# NovaHammyRevXD.net
KiCad netlist of a schematic drawn in EAGLE
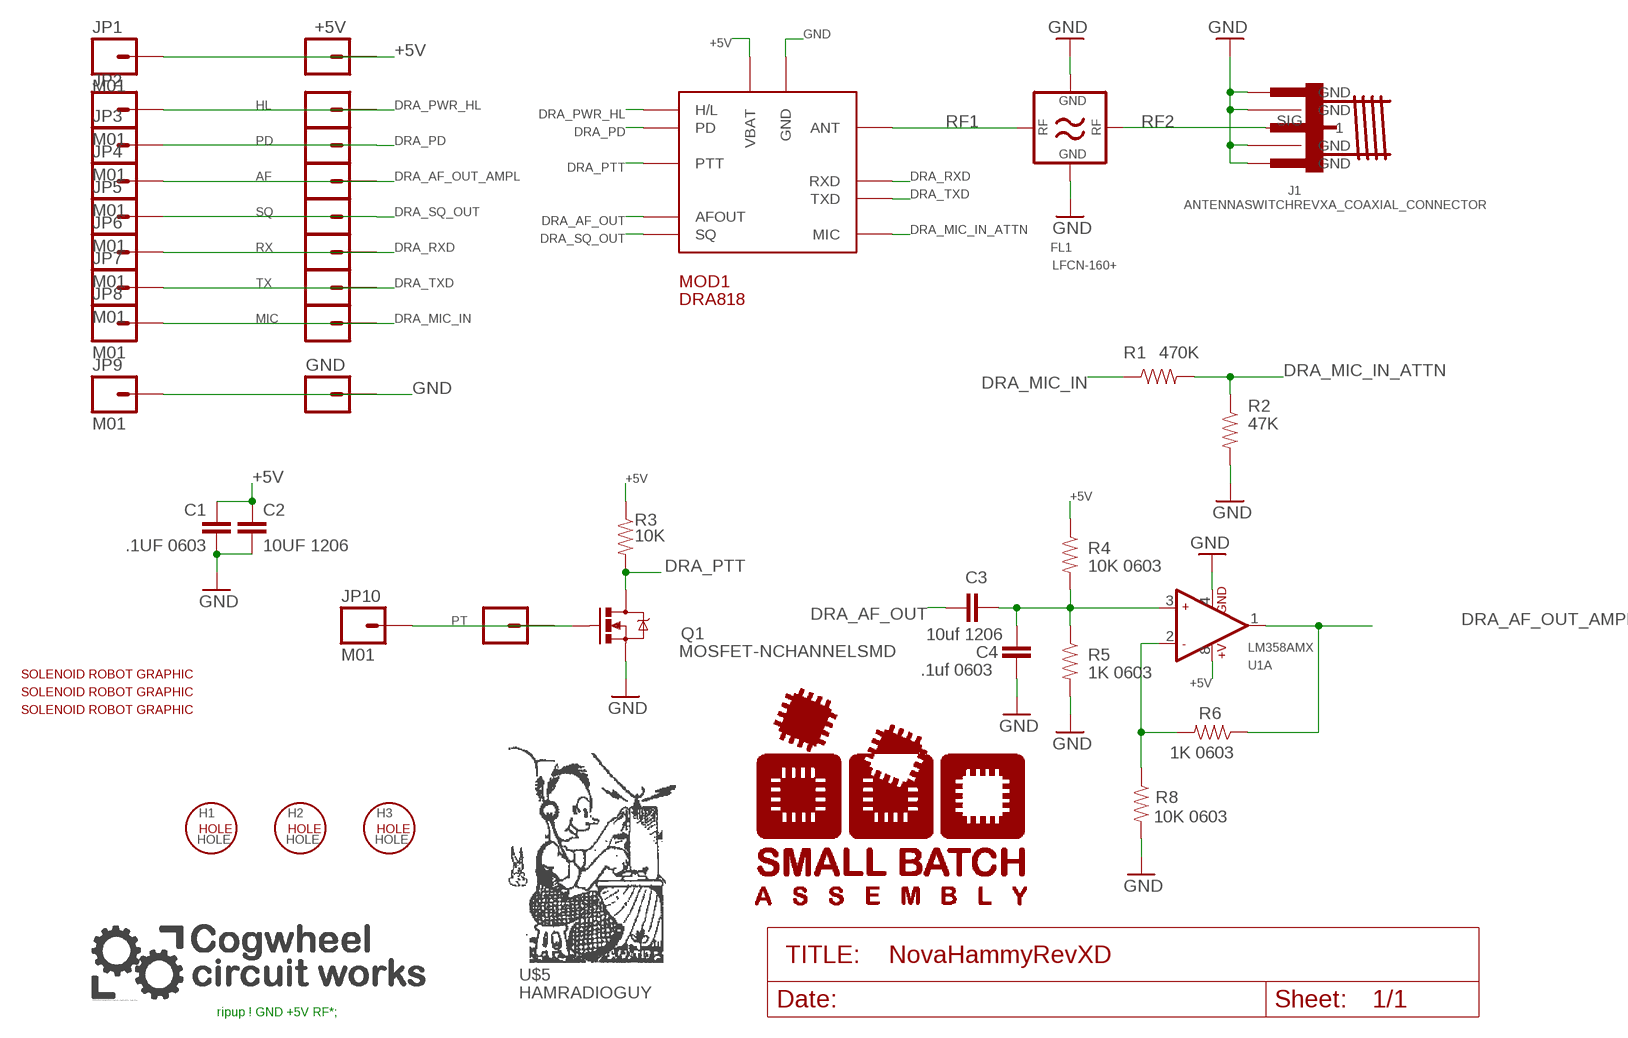
[diagram p0: schematic, sheet 1]

(export (version "E")
  (design (tool "Eeschema 10.0.6"))
  (components
    (comp (ref "5V")
      (value "+5V")
      (footprint "eagle-import:1X01_NO_SILK")
      (libsource (lib "eagle-import") (part "M01PTH_NO_SILK_YES_STOP"))
    )
    (comp (ref "AF")
      (value "M01PTH_NO_SILK_YES_STOP")
      (footprint "eagle-import:1X01_NO_SILK")
      (libsource (lib "eagle-import") (part "M01PTH_NO_SILK_YES_STOP"))
    )
    (comp (ref "C1")
      (value ".1UF 0603")
      (footprint "eagle-import:0603")
      (libsource (lib "eagle-import") (part "CAP0603"))
    )
    (comp (ref "C2")
      (value "10UF 1206")
      (footprint "eagle-import:1206")
      (libsource (lib "eagle-import") (part "CAP1206"))
    )
    (comp (ref "C3")
      (value "10uf 1206")
      (footprint "eagle-import:1206")
      (libsource (lib "eagle-import") (part "CAP1206"))
    )
    (comp (ref "C4")
      (value ".1uf 0603")
      (footprint "eagle-import:0603")
      (libsource (lib "eagle-import") (part "CAP0603"))
    )
    (comp (ref "FL1")
      (value "LFCN-160+")
      (footprint "eagle-import:FV1206")
      (libsource (lib "eagle-import") (part "LFCN-XXX"))
    )
    (comp (ref "GND")
      (value "M01PTH_NO_SILK_YES_STOP")
      (footprint "eagle-import:1X01_NO_SILK")
      (libsource (lib "eagle-import") (part "M01PTH_NO_SILK_YES_STOP"))
    )
    (comp (ref "H1")
      (value "HOLE")
      (footprint "eagle-import:HOLE_3.3MM_M3_HEX_BOLT")
      (libsource (lib "eagle-import") (part "HOLE"))
    )
    (comp (ref "H2")
      (value "HOLE")
      (footprint "eagle-import:HOLE_3.3MM_M3_HEX_BOLT")
      (libsource (lib "eagle-import") (part "HOLE"))
    )
    (comp (ref "H3")
      (value "HOLE")
      (footprint "eagle-import:HOLE_3.3MM_M3_HEX_BOLT")
      (libsource (lib "eagle-import") (part "HOLE"))
    )
    (comp (ref "HL")
      (value "M01PTH_NO_SILK_YES_STOP")
      (footprint "eagle-import:1X01_NO_SILK")
      (libsource (lib "eagle-import") (part "M01PTH_NO_SILK_YES_STOP"))
    )
    (comp (ref "J1")
      (value "ANTENNASWITCHREVXA_COAXIAL_CONNECTOR")
      (footprint "eagle-import:ANTENNASWITCHREVXA_SMA_JACK_EDGE_MOUNT")
      (libsource (lib "eagle-import") (part "ANTENNASWITCHREVXA_COAXIAL_CONNECTOR"))
    )
    (comp (ref "JP1")
      (value "M01")
      (footprint "eagle-import:1X01_SMT_2MM")
      (libsource (lib "eagle-import") (part "M01"))
    )
    (comp (ref "JP2")
      (value "M01")
      (footprint "eagle-import:1X01_SMT_2MM")
      (libsource (lib "eagle-import") (part "M01"))
    )
    (comp (ref "JP3")
      (value "M01")
      (footprint "eagle-import:1X01_SMT_2MM")
      (libsource (lib "eagle-import") (part "M01"))
    )
    (comp (ref "JP4")
      (value "M01")
      (footprint "eagle-import:1X01_SMT_2MM")
      (libsource (lib "eagle-import") (part "M01"))
    )
    (comp (ref "JP5")
      (value "M01")
      (footprint "eagle-import:1X01_SMT_2MM")
      (libsource (lib "eagle-import") (part "M01"))
    )
    (comp (ref "JP6")
      (value "M01")
      (footprint "eagle-import:1X01_SMT_2MM")
      (libsource (lib "eagle-import") (part "M01"))
    )
    (comp (ref "JP7")
      (value "M01")
      (footprint "eagle-import:1X01_SMT_2MM")
      (libsource (lib "eagle-import") (part "M01"))
    )
    (comp (ref "JP8")
      (value "M01")
      (footprint "eagle-import:1X01_SMT_2MM")
      (libsource (lib "eagle-import") (part "M01"))
    )
    (comp (ref "JP9")
      (value "M01")
      (footprint "eagle-import:1X01_SMT_2MM")
      (libsource (lib "eagle-import") (part "M01"))
    )
    (comp (ref "JP10")
      (value "M01")
      (footprint "eagle-import:1X01_SMT_2MM")
      (libsource (lib "eagle-import") (part "M01"))
    )
    (comp (ref "MIC")
      (value "M01PTH_NO_SILK_YES_STOP")
      (footprint "eagle-import:1X01_NO_SILK")
      (libsource (lib "eagle-import") (part "M01PTH_NO_SILK_YES_STOP"))
    )
    (comp (ref "MOD1")
      (value "DRA818")
      (footprint "eagle-import:DRA818")
      (libsource (lib "eagle-import") (part "DRA818"))
    )
    (comp (ref "PD")
      (value "M01PTH_NO_SILK_YES_STOP")
      (footprint "eagle-import:1X01_NO_SILK")
      (libsource (lib "eagle-import") (part "M01PTH_NO_SILK_YES_STOP"))
    )
    (comp (ref "PT")
      (value "M01PTH_NO_SILK_YES_STOP")
      (footprint "eagle-import:1X01_NO_SILK")
      (libsource (lib "eagle-import") (part "M01PTH_NO_SILK_YES_STOP"))
    )
    (comp (ref "Q1")
      (value "MOSFET-NCHANNELSMD")
      (footprint "eagle-import:SOT23-3")
      (libsource (lib "eagle-import") (part "MOSFET-NCHANNELSMD"))
    )
    (comp (ref "R1")
      (value "470K")
      (footprint "eagle-import:0603")
      (libsource (lib "eagle-import") (part "RES0603"))
    )
    (comp (ref "R2")
      (value "47K")
      (footprint "eagle-import:0603")
      (libsource (lib "eagle-import") (part "RES0603"))
    )
    (comp (ref "R3")
      (value "10K")
      (footprint "eagle-import:0603")
      (libsource (lib "eagle-import") (part "RES0603"))
    )
    (comp (ref "R4")
      (value "10K 0603")
      (footprint "eagle-import:0603")
      (libsource (lib "eagle-import") (part "RES0603"))
    )
    (comp (ref "R5")
      (value "1K 0603")
      (footprint "eagle-import:0603")
      (libsource (lib "eagle-import") (part "RES0603"))
    )
    (comp (ref "R6")
      (value "1K 0603")
      (footprint "eagle-import:0603")
      (libsource (lib "eagle-import") (part "RES0603"))
    )
    (comp (ref "R8")
      (value "10K 0603")
      (footprint "eagle-import:0603")
      (libsource (lib "eagle-import") (part "RES0603"))
    )
    (comp (ref "RX")
      (value "M01PTH_NO_SILK_YES_STOP")
      (footprint "eagle-import:1X01_NO_SILK")
      (libsource (lib "eagle-import") (part "M01PTH_NO_SILK_YES_STOP"))
    )
    (comp (ref "SQ")
      (value "M01PTH_NO_SILK_YES_STOP")
      (footprint "eagle-import:1X01_NO_SILK")
      (libsource (lib "eagle-import") (part "M01PTH_NO_SILK_YES_STOP"))
    )
    (comp (ref "TX")
      (value "M01PTH_NO_SILK_YES_STOP")
      (footprint "eagle-import:1X01_NO_SILK")
      (libsource (lib "eagle-import") (part "M01PTH_NO_SILK_YES_STOP"))
    )
    (comp (ref "U$1")
      (value "SOLENOID_ROBOTSML")
      (footprint "eagle-import:SOLENOID_ROBOT")
      (libsource (lib "eagle-import") (part "SOLENOID_ROBOTSML"))
    )
    (comp (ref "U$2")
      (value "SOLENOID_ROBOTSML")
      (footprint "eagle-import:SOLENOID_ROBOT")
      (libsource (lib "eagle-import") (part "SOLENOID_ROBOTSML"))
    )
    (comp (ref "U$3")
      (value "SOLENOID_ROBOTSML")
      (footprint "eagle-import:SOLENOID_ROBOT")
      (libsource (lib "eagle-import") (part "SOLENOID_ROBOTSML"))
    )
    (comp (ref "U$4")
      (value "SMALLBATCH_LOGOA")
      (footprint "eagle-import:SMALLBATCH_750W_V2")
      (libsource (lib "eagle-import") (part "SMALLBATCH_LOGOA"))
    )
    (comp (ref "U$5")
      (value "HAMRADIOGUY")
      (footprint "eagle-import:HAMRADIO_3Q_INCH")
      (libsource (lib "eagle-import") (part "HAMRADIOGUY"))
    )
    (comp (ref "U$6")
      (value "CWILOGO")
      (footprint "eagle-import:CWORKSLOGO_750MIL_WIDE_400DPI")
      (libsource (lib "eagle-import") (part "CWILOGO"))
    )
    (comp (ref "U1")
      (value "LM358AMX")
      (footprint "eagle-import:SOIC8")
      (libsource (lib "eagle-import") (part "LM358DR-1110010P1"))
    )
  )
  (nets
    (net (code "1") (name "/+5V") (class "Default")
      (node (ref "5V") (pin "1") (pinfunction "1_1") (pintype "passive"))
      (node (ref "C1") (pin "2") (pinfunction "2_2") (pintype "passive"))
      (node (ref "C2") (pin "1") (pinfunction "1_1") (pintype "passive"))
      (node (ref "JP1") (pin "P$1") (pinfunction "1_P$1") (pintype "passive"))
      (node (ref "MOD1") (pin "P$8") (pinfunction "VBAT_P$8") (pintype "bidirectional"))
      (node (ref "R3") (pin "1") (pinfunction "1_1") (pintype "passive"))
      (node (ref "R4") (pin "1") (pinfunction "1_1") (pintype "passive"))
      (node (ref "U1") (pin "8") (pinfunction "+V_8") (pintype "power_in"))
    )
    (net (code "2") (name "/DRA_AF_OUT") (class "Default")
      (node (ref "C3") (pin "1") (pinfunction "1_1") (pintype "passive"))
      (node (ref "MOD1") (pin "P$3") (pinfunction "AFOUT_P$3") (pintype "bidirectional"))
    )
    (net (code "3") (name "/DRA_AF_OUT_AMPL") (class "Default")
      (node (ref "AF") (pin "1") (pinfunction "1_1") (pintype "passive"))
      (node (ref "JP4") (pin "P$1") (pinfunction "1_P$1") (pintype "passive"))
      (node (ref "R6") (pin "1") (pinfunction "1_1") (pintype "passive"))
      (node (ref "U1") (pin "1") (pinfunction "OUT1_1") (pintype "output"))
    )
    (net (code "4") (name "/DRA_MIC_IN") (class "Default")
      (node (ref "JP8") (pin "P$1") (pinfunction "1_P$1") (pintype "passive"))
      (node (ref "MIC") (pin "1") (pinfunction "1_1") (pintype "passive"))
      (node (ref "R1") (pin "1") (pinfunction "1_1") (pintype "passive"))
    )
    (net (code "5") (name "/DRA_MIC_IN_ATTN") (class "Default")
      (node (ref "MOD1") (pin "P$18") (pinfunction "MIC_P$18") (pintype "bidirectional"))
      (node (ref "R1") (pin "2") (pinfunction "2_2") (pintype "passive"))
      (node (ref "R2") (pin "1") (pinfunction "1_1") (pintype "passive"))
    )
    (net (code "6") (name "/DRA_PD") (class "Default")
      (node (ref "JP3") (pin "P$1") (pinfunction "1_P$1") (pintype "passive"))
      (node (ref "MOD1") (pin "P$6") (pinfunction "PD_P$6") (pintype "bidirectional"))
      (node (ref "PD") (pin "1") (pinfunction "1_1") (pintype "passive"))
    )
    (net (code "7") (name "/DRA_PTT") (class "Default")
      (node (ref "MOD1") (pin "P$5") (pinfunction "PTT_P$5") (pintype "bidirectional"))
      (node (ref "Q1") (pin "3") (pinfunction "D_3") (pintype "passive"))
      (node (ref "R3") (pin "2") (pinfunction "2_2") (pintype "passive"))
    )
    (net (code "8") (name "/DRA_PWR_HL") (class "Default")
      (node (ref "HL") (pin "1") (pinfunction "1_1") (pintype "passive"))
      (node (ref "JP2") (pin "P$1") (pinfunction "1_P$1") (pintype "passive"))
      (node (ref "MOD1") (pin "P$7") (pinfunction "H/L_P$7") (pintype "bidirectional"))
    )
    (net (code "9") (name "/DRA_RXD") (class "Default")
      (node (ref "JP6") (pin "P$1") (pinfunction "1_P$1") (pintype "passive"))
      (node (ref "MOD1") (pin "P$16") (pinfunction "RXD_P$16") (pintype "bidirectional"))
      (node (ref "RX") (pin "1") (pinfunction "1_1") (pintype "passive"))
    )
    (net (code "10") (name "/DRA_SQ_OUT") (class "Default")
      (node (ref "JP5") (pin "P$1") (pinfunction "1_P$1") (pintype "passive"))
      (node (ref "MOD1") (pin "P$1") (pinfunction "SQ_P$1") (pintype "bidirectional"))
      (node (ref "SQ") (pin "1") (pinfunction "1_1") (pintype "passive"))
    )
    (net (code "11") (name "/DRA_TXD") (class "Default")
      (node (ref "JP7") (pin "P$1") (pinfunction "1_P$1") (pintype "passive"))
      (node (ref "MOD1") (pin "P$17") (pinfunction "TXD_P$17") (pintype "bidirectional"))
      (node (ref "TX") (pin "1") (pinfunction "1_1") (pintype "passive"))
    )
    (net (code "12") (name "/RF1") (class "Default")
      (node (ref "FL1") (pin "1") (pinfunction "IO1_1") (pintype "passive"))
      (node (ref "MOD1") (pin "P$12") (pinfunction "ANT_P$12") (pintype "bidirectional"))
    )
    (net (code "13") (name "/RF2") (class "Default")
      (node (ref "FL1") (pin "3") (pinfunction "IO2_3") (pintype "passive"))
      (node (ref "J1") (pin "SIG") (pinfunction "1_SIG") (pintype "passive"))
    )
    (net (code "14") (name "GND") (class "Default")
      (node (ref "C1") (pin "1") (pinfunction "1_1") (pintype "passive"))
      (node (ref "C2") (pin "2") (pinfunction "2_2") (pintype "passive"))
      (node (ref "C4") (pin "2") (pinfunction "2_2") (pintype "passive"))
      (node (ref "FL1") (pin "11") (pinfunction "GND2_11") (pintype "passive"))
      (node (ref "FL1") (pin "12") (pinfunction "GND2_12") (pintype "passive"))
      (node (ref "FL1") (pin "13") (pinfunction "GND2_13") (pintype "passive"))
      (node (ref "FL1") (pin "14") (pinfunction "GND2_14") (pintype "passive"))
      (node (ref "FL1") (pin "2") (pinfunction "GND2_2") (pintype "passive"))
      (node (ref "FL1") (pin "4") (pinfunction "GND1_4") (pintype "passive"))
      (node (ref "FL1") (pin "6") (pinfunction "GND1_6") (pintype "passive"))
      (node (ref "FL1") (pin "7") (pinfunction "GND1_7") (pintype "passive"))
      (node (ref "FL1") (pin "8") (pinfunction "GND1_8") (pintype "passive"))
      (node (ref "FL1") (pin "9") (pinfunction "GND1_9") (pintype "passive"))
      (node (ref "GND") (pin "1") (pinfunction "1_1") (pintype "passive"))
      (node (ref "J1") (pin "G") (pinfunction "GND_G") (pintype "passive"))
      (node (ref "J1") (pin "G2") (pinfunction "GND_G2") (pintype "passive"))
      (node (ref "J1") (pin "G3") (pinfunction "GND_G3") (pintype "passive"))
      (node (ref "J1") (pin "G4") (pinfunction "GND_G4") (pintype "passive"))
      (node (ref "JP9") (pin "P$1") (pinfunction "1_P$1") (pintype "passive"))
      (node (ref "MOD1") (pin "P$10") (pinfunction "GND_P$10") (pintype "bidirectional"))
      (node (ref "MOD1") (pin "P$9") (pinfunction "GND_P$9") (pintype "bidirectional"))
      (node (ref "Q1") (pin "2") (pinfunction "S_2") (pintype "passive"))
      (node (ref "R2") (pin "2") (pinfunction "2_2") (pintype "passive"))
      (node (ref "R5") (pin "2") (pinfunction "2_2") (pintype "passive"))
      (node (ref "R8") (pin "2") (pinfunction "2_2") (pintype "passive"))
      (node (ref "U1") (pin "4") (pinfunction "GND_4") (pintype "power_in"))
    )
    (net (code "15") (name "Net-(JP10-1)") (class "Default")
      (node (ref "JP10") (pin "P$1") (pinfunction "1_P$1") (pintype "passive"))
      (node (ref "PT") (pin "1") (pinfunction "1_1") (pintype "passive"))
      (node (ref "Q1") (pin "1") (pinfunction "G_1") (pintype "passive"))
    )
    (net (code "16") (name "Net-(U1A-+IN1)") (class "Default")
      (node (ref "C3") (pin "2") (pinfunction "2_2") (pintype "passive"))
      (node (ref "C4") (pin "1") (pinfunction "1_1") (pintype "passive"))
      (node (ref "R4") (pin "2") (pinfunction "2_2") (pintype "passive"))
      (node (ref "R5") (pin "1") (pinfunction "1_1") (pintype "passive"))
      (node (ref "U1") (pin "3") (pinfunction "+IN1_3") (pintype "input"))
    )
    (net (code "17") (name "Net-(U1A--IN1)") (class "Default")
      (node (ref "R6") (pin "2") (pinfunction "2_2") (pintype "passive"))
      (node (ref "R8") (pin "1") (pinfunction "1_1") (pintype "passive"))
      (node (ref "U1") (pin "2") (pinfunction "-IN1_2") (pintype "input"))
    )
  )
)
